# Neopixel.net
KiCad netlist of a schematic drawn in Altium Designer
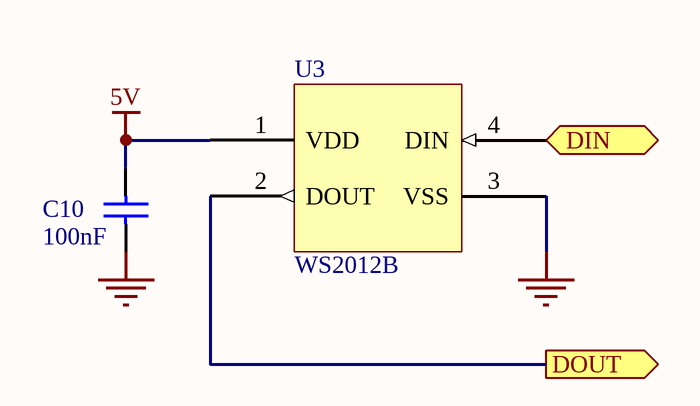
[diagram p0: Neopixel.SchDoc]

(export (version "E")
  (design (tool "Eeschema 10.0.6"))
  (components
    (comp (ref "C10")
      (value "100nF")
      (footprint "CAP0603")
      (description "Capacitor")
      (libsource (lib "Miscellaneous Devices") (part "Cap"))
    )
    (comp (ref "U3")
      (value "WS2012B")
      (footprint "WS2812b")
      (description "Neopixel")
      (libsource (lib "Components") (part "WS2012B"))
    )
  )
  (nets
    (net (code "1") (name "/DIN") (class "Default")
      (node (ref "U3") (pin "4") (pinfunction "DIN_4") (pintype "input"))
    )
    (net (code "2") (name "/DOUT") (class "Default")
      (node (ref "U3") (pin "2") (pinfunction "DOUT_2") (pintype "output"))
    )
    (net (code "3") (name "5V") (class "Default")
      (node (ref "C10") (pin "2") (pinfunction "2_2") (pintype "passive"))
      (node (ref "U3") (pin "1") (pinfunction "VDD_1") (pintype "power_in"))
    )
    (net (code "4") (name "VSS") (class "Default")
      (node (ref "C10") (pin "1") (pinfunction "1_1") (pintype "passive"))
      (node (ref "U3") (pin "3") (pinfunction "VSS_3") (pintype "power_in"))
    )
  )
)
